# gsm.net
KiCad netlist of a schematic drawn in EAGLE
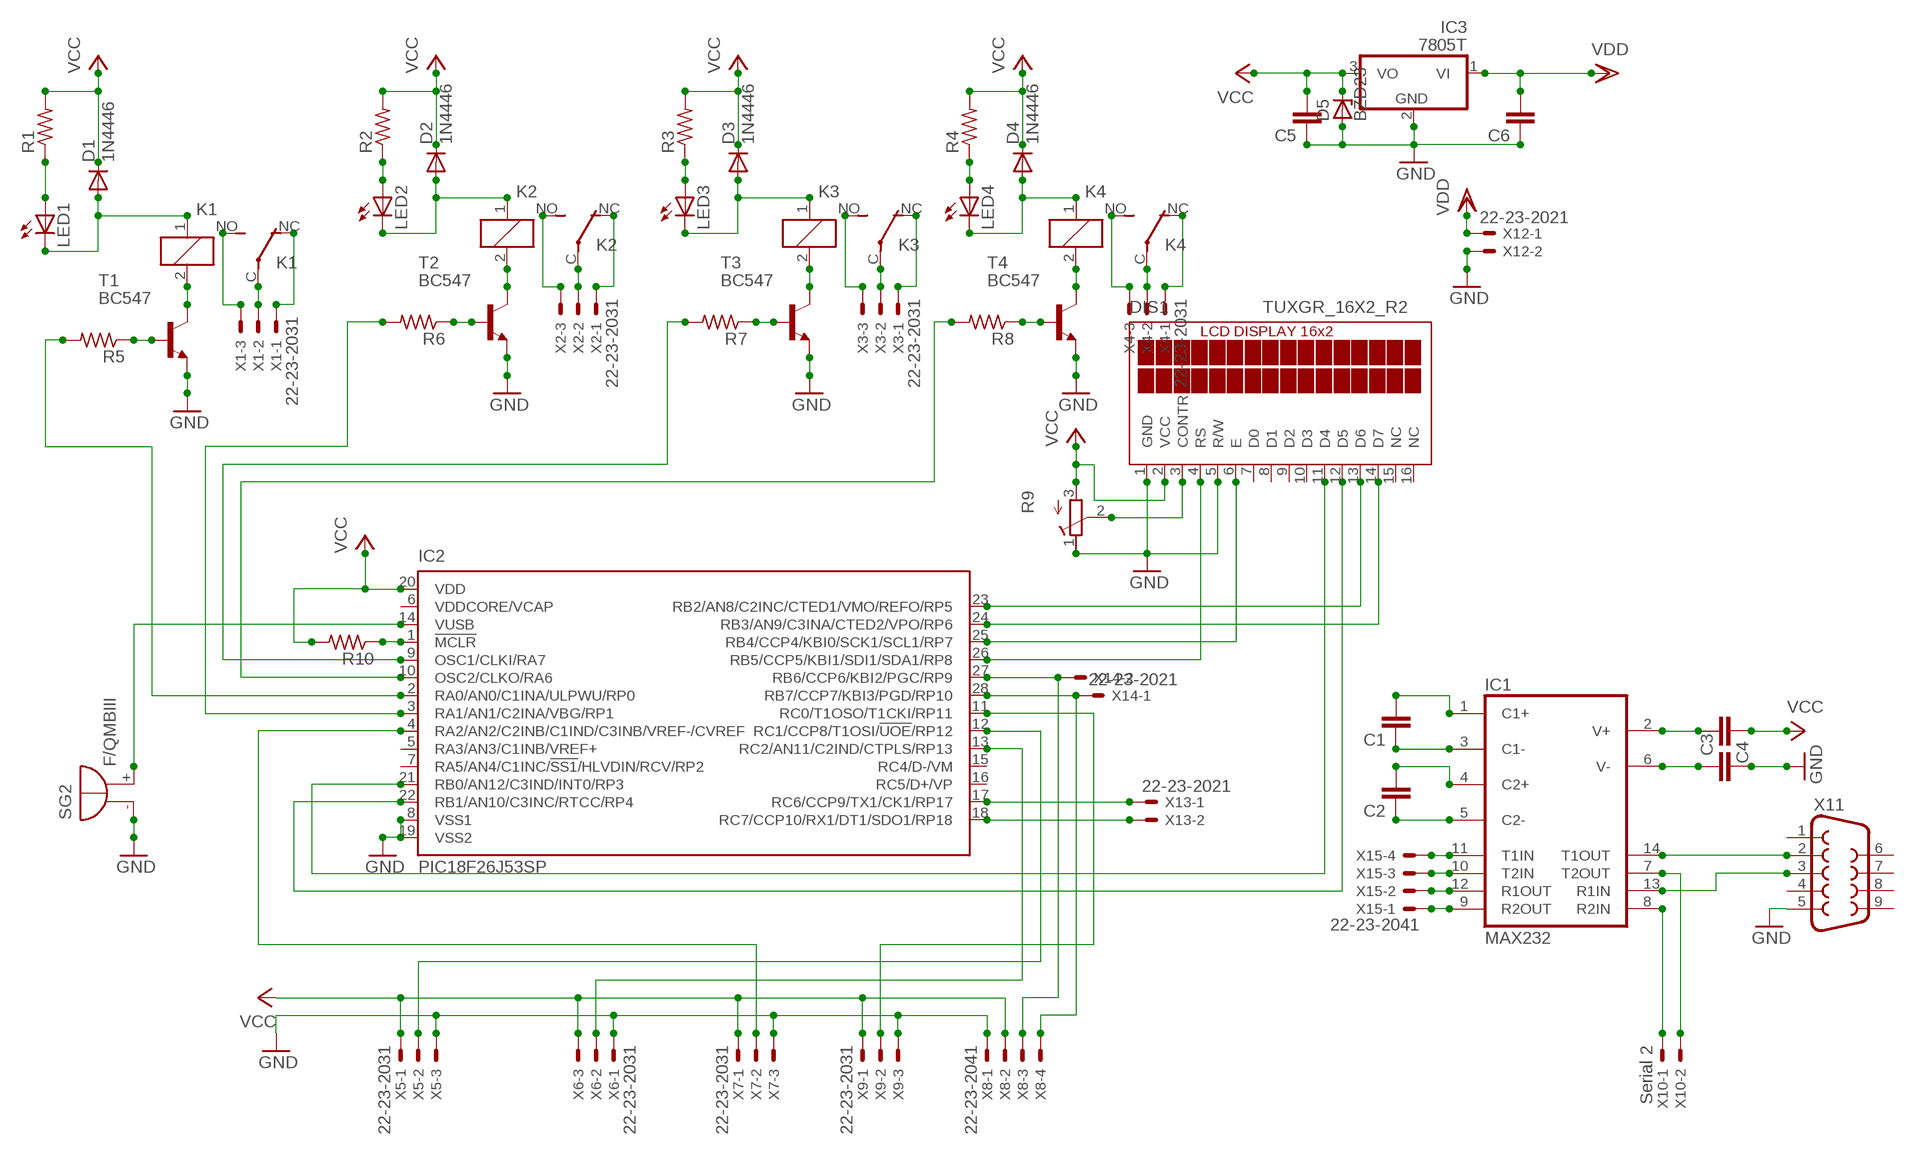
[diagram p0: schematic, sheet 1]

(export (version "E")
  (design (tool "Eeschema 10.0.6"))
  (components
    (comp (ref "C1")
      (value "C2.5/2")
      (footprint "eagle-import:C2.5-2")
      (libsource (lib "eagle-import") (part "C2.5/2"))
    )
    (comp (ref "C2")
      (value "C2.5/2")
      (footprint "eagle-import:C2.5-2")
      (libsource (lib "eagle-import") (part "C2.5/2"))
    )
    (comp (ref "C3")
      (value "C2.5/2")
      (footprint "eagle-import:C2.5-2")
      (libsource (lib "eagle-import") (part "C2.5/2"))
    )
    (comp (ref "C4")
      (value "C2.5/2")
      (footprint "eagle-import:C2.5-2")
      (libsource (lib "eagle-import") (part "C2.5/2"))
    )
    (comp (ref "C5")
      (value "C2.5/2")
      (footprint "eagle-import:C2.5-2")
      (libsource (lib "eagle-import") (part "C2.5/2"))
    )
    (comp (ref "C6")
      (value "C2.5/2")
      (footprint "eagle-import:C2.5-2")
      (libsource (lib "eagle-import") (part "C2.5/2"))
    )
    (comp (ref "D1")
      (value "1N4446")
      (footprint "eagle-import:DO35-10")
      (libsource (lib "eagle-import") (part "1N4446"))
    )
    (comp (ref "D2")
      (value "1N4446")
      (footprint "eagle-import:DO35-10")
      (libsource (lib "eagle-import") (part "1N4446"))
    )
    (comp (ref "D3")
      (value "1N4446")
      (footprint "eagle-import:DO35-10")
      (libsource (lib "eagle-import") (part "1N4446"))
    )
    (comp (ref "D4")
      (value "1N4446")
      (footprint "eagle-import:DO35-10")
      (libsource (lib "eagle-import") (part "1N4446"))
    )
    (comp (ref "D5")
      (value "BZD23")
      (footprint "eagle-import:SOD81")
      (libsource (lib "eagle-import") (part "BZD23"))
    )
    (comp (ref "DIS1")
      (value "TUXGR_16X2_R2")
      (footprint "eagle-import:TUXGR_16X2_R2")
      (libsource (lib "eagle-import") (part "TUXGR_16X2_R2"))
    )
    (comp (ref "IC1")
      (value "MAX232")
      (footprint "eagle-import:DIL16")
      (fields (field (name "MF") "MAXIM") (field (name "MPN") "MAX232ACPE+"))
      (libsource (lib "eagle-import") (part "MAX232"))
    )
    (comp (ref "IC2")
      (value "PIC18F26J53SP")
      (footprint "eagle-import:DIL28-3")
      (fields (field (name "MPN") "PIC18F26J53-I/SP"))
      (libsource (lib "eagle-import") (part "PIC18F2J53SP6"))
    )
    (comp (ref "IC3")
      (value "7805T")
      (footprint "eagle-import:TO220H")
      (libsource (lib "eagle-import") (part "78T05"))
    )
    (comp (ref "K1")
      (value "JJM1-12V")
      (footprint "eagle-import:JJM1C")
      (fields (field (name "MF") "AROMAT/ MATSUSHITA"))
      (libsource (lib "eagle-import") (part "JJM1-12V"))
    )
    (comp (ref "K2")
      (value "JJM1-12V")
      (footprint "eagle-import:JJM1C")
      (fields (field (name "MF") "AROMAT/ MATSUSHITA"))
      (libsource (lib "eagle-import") (part "JJM1-12V"))
    )
    (comp (ref "K3")
      (value "JJM1-12V")
      (footprint "eagle-import:JJM1C")
      (fields (field (name "MF") "AROMAT/ MATSUSHITA"))
      (libsource (lib "eagle-import") (part "JJM1-12V"))
    )
    (comp (ref "K4")
      (value "JJM1-12V")
      (footprint "eagle-import:JJM1C")
      (fields (field (name "MF") "AROMAT/ MATSUSHITA"))
      (libsource (lib "eagle-import") (part "JJM1-12V"))
    )
    (comp (ref "LED1")
      (value "LED3MM")
      (footprint "eagle-import:LED3MM")
      (libsource (lib "eagle-import") (part "LED3MM"))
    )
    (comp (ref "LED2")
      (value "LED3MM")
      (footprint "eagle-import:LED3MM")
      (libsource (lib "eagle-import") (part "LED3MM"))
    )
    (comp (ref "LED3")
      (value "LED3MM")
      (footprint "eagle-import:LED3MM")
      (libsource (lib "eagle-import") (part "LED3MM"))
    )
    (comp (ref "LED4")
      (value "LED3MM")
      (footprint "eagle-import:LED3MM")
      (libsource (lib "eagle-import") (part "LED3MM"))
    )
    (comp (ref "R1")
      (value "R-US_0207/10")
      (footprint "eagle-import:0207_10")
      (libsource (lib "eagle-import") (part "R-US_0207/10"))
    )
    (comp (ref "R2")
      (value "R-US_0207/10")
      (footprint "eagle-import:0207_10")
      (libsource (lib "eagle-import") (part "R-US_0207/10"))
    )
    (comp (ref "R3")
      (value "R-US_0207/10")
      (footprint "eagle-import:0207_10")
      (libsource (lib "eagle-import") (part "R-US_0207/10"))
    )
    (comp (ref "R4")
      (value "R-US_0207/10")
      (footprint "eagle-import:0207_10")
      (libsource (lib "eagle-import") (part "R-US_0207/10"))
    )
    (comp (ref "R5")
      (value "R-US_0207/10")
      (footprint "eagle-import:0207_10")
      (libsource (lib "eagle-import") (part "R-US_0207/10"))
    )
    (comp (ref "R6")
      (value "R-US_0207/10")
      (footprint "eagle-import:0207_10")
      (libsource (lib "eagle-import") (part "R-US_0207/10"))
    )
    (comp (ref "R7")
      (value "R-US_0207/10")
      (footprint "eagle-import:0207_10")
      (libsource (lib "eagle-import") (part "R-US_0207/10"))
    )
    (comp (ref "R8")
      (value "R-US_0207/10")
      (footprint "eagle-import:0207_10")
      (libsource (lib "eagle-import") (part "R-US_0207/10"))
    )
    (comp (ref "R9")
      (value "R-TRIMMT93YA")
      (footprint "eagle-import:RTRIMT93YA")
      (libsource (lib "eagle-import") (part "R-TRIMMT93YA"))
    )
    (comp (ref "R10")
      (value "R-US_0207/10")
      (footprint "eagle-import:0207_10")
      (libsource (lib "eagle-import") (part "R-US_0207/10"))
    )
    (comp (ref "SG2")
      (value "F/QMBIII")
      (footprint "eagle-import:F_QMBIII")
      (libsource (lib "eagle-import") (part "F/QMBIII"))
    )
    (comp (ref "T1")
      (value "BC547")
      (footprint "eagle-import:TO92")
      (libsource (lib "eagle-import") (part "BC547"))
    )
    (comp (ref "T2")
      (value "BC547")
      (footprint "eagle-import:TO92")
      (libsource (lib "eagle-import") (part "BC547"))
    )
    (comp (ref "T3")
      (value "BC547")
      (footprint "eagle-import:TO92")
      (libsource (lib "eagle-import") (part "BC547"))
    )
    (comp (ref "T4")
      (value "BC547")
      (footprint "eagle-import:TO92")
      (libsource (lib "eagle-import") (part "BC547"))
    )
    (comp (ref "X1")
      (value "22-23-2031")
      (footprint "eagle-import:22-23-2031")
      (fields (field (name "MF") "MOLEX"))
      (libsource (lib "eagle-import") (part "22-23-2031"))
    )
    (comp (ref "X2")
      (value "22-23-2031")
      (footprint "eagle-import:22-23-2031")
      (fields (field (name "MF") "MOLEX"))
      (libsource (lib "eagle-import") (part "22-23-2031"))
    )
    (comp (ref "X3")
      (value "22-23-2031")
      (footprint "eagle-import:22-23-2031")
      (fields (field (name "MF") "MOLEX"))
      (libsource (lib "eagle-import") (part "22-23-2031"))
    )
    (comp (ref "X4")
      (value "22-23-2031")
      (footprint "eagle-import:22-23-2031")
      (fields (field (name "MF") "MOLEX"))
      (libsource (lib "eagle-import") (part "22-23-2031"))
    )
    (comp (ref "X5")
      (value "22-23-2031")
      (footprint "eagle-import:22-23-2031")
      (fields (field (name "MF") "MOLEX"))
      (libsource (lib "eagle-import") (part "22-23-2031"))
    )
    (comp (ref "X6")
      (value "22-23-2031")
      (footprint "eagle-import:22-23-2031")
      (fields (field (name "MF") "MOLEX"))
      (libsource (lib "eagle-import") (part "22-23-2031"))
    )
    (comp (ref "X7")
      (value "22-23-2031")
      (footprint "eagle-import:22-23-2031")
      (fields (field (name "MF") "MOLEX"))
      (libsource (lib "eagle-import") (part "22-23-2031"))
    )
    (comp (ref "X8")
      (value "22-23-2041")
      (footprint "eagle-import:22-23-2041")
      (fields (field (name "MF") "MOLEX"))
      (libsource (lib "eagle-import") (part "22-23-2041"))
    )
    (comp (ref "X9")
      (value "22-23-2031")
      (footprint "eagle-import:22-23-2031")
      (fields (field (name "MF") "MOLEX"))
      (libsource (lib "eagle-import") (part "22-23-2031"))
    )
    (comp (ref "X10")
      (value "Serial 2")
      (footprint "eagle-import:22-23-2021")
      (fields (field (name "MF") "MOLEX") (field (name "MPN") "22-23-2021"))
      (libsource (lib "eagle-import") (part "22-23-2021"))
    )
    (comp (ref "X11")
      (value "F09H")
      (footprint "eagle-import:F09H")
      (libsource (lib "eagle-import") (part "F09H"))
    )
    (comp (ref "X12")
      (value "22-23-2021")
      (footprint "eagle-import:22-23-2021")
      (fields (field (name "MF") "MOLEX"))
      (libsource (lib "eagle-import") (part "22-23-2021"))
    )
    (comp (ref "X13")
      (value "22-23-2021")
      (footprint "eagle-import:22-23-2021")
      (fields (field (name "MF") "MOLEX"))
      (libsource (lib "eagle-import") (part "22-23-2021"))
    )
    (comp (ref "X14")
      (value "22-23-2021")
      (footprint "eagle-import:22-23-2021")
      (fields (field (name "MF") "MOLEX"))
      (libsource (lib "eagle-import") (part "22-23-2021"))
    )
    (comp (ref "X15")
      (value "22-23-2041")
      (footprint "eagle-import:22-23-2041")
      (fields (field (name "MF") "MOLEX"))
      (libsource (lib "eagle-import") (part "22-23-2041"))
    )
  )
  (nets
    (net (code "1") (name "GND") (class "Default")
      (node (ref "C3") (pin "2") (pinfunction "2_2") (pintype "passive"))
      (node (ref "C5") (pin "1") (pinfunction "1_1") (pintype "passive"))
      (node (ref "C6") (pin "1") (pinfunction "1_1") (pintype "passive"))
      (node (ref "D5") (pin "A") (pinfunction "A_A") (pintype "passive"))
      (node (ref "DIS1") (pin "1") (pinfunction "GND_1") (pintype "power_in"))
      (node (ref "DIS1") (pin "5") (pinfunction "R/W_5") (pintype "input"))
      (node (ref "IC2") (pin "19") (pinfunction "VSS2_19") (pintype "input"))
      (node (ref "IC2") (pin "8") (pinfunction "VSS1_8") (pintype "input"))
      (node (ref "IC3") (pin "2") (pinfunction "GND_2") (pintype "passive"))
      (node (ref "R9") (pin "1") (pinfunction "E_1") (pintype "passive"))
      (node (ref "SG2") (pin "-") (pinfunction "+_-") (pintype "passive"))
      (node (ref "T1") (pin "1") (pinfunction "E_1") (pintype "passive"))
      (node (ref "T2") (pin "1") (pinfunction "E_1") (pintype "passive"))
      (node (ref "T3") (pin "1") (pinfunction "E_1") (pintype "passive"))
      (node (ref "T4") (pin "1") (pinfunction "E_1") (pintype "passive"))
      (node (ref "X11") (pin "5") (pinfunction "5_5") (pintype "passive"))
      (node (ref "X12") (pin "2") (pinfunction "S_2") (pintype "passive"))
      (node (ref "X5") (pin "3") (pinfunction "S_3") (pintype "passive"))
      (node (ref "X6") (pin "1") (pinfunction "S_1") (pintype "passive"))
      (node (ref "X7") (pin "3") (pinfunction "S_3") (pintype "passive"))
      (node (ref "X8") (pin "1") (pinfunction "S_1") (pintype "passive"))
      (node (ref "X9") (pin "3") (pinfunction "S_3") (pintype "passive"))
    )
    (net (code "2") (name "Net-(DIS1-CONTR)") (class "Default")
      (node (ref "DIS1") (pin "3") (pinfunction "CONTR_3") (pintype "input"))
      (node (ref "R9") (pin "2") (pinfunction "S_2") (pintype "passive"))
    )
    (net (code "3") (name "Net-(DIS1-D4)") (class "Default")
      (node (ref "DIS1") (pin "11") (pinfunction "D4_11") (pintype "input"))
      (node (ref "IC2") (pin "21") (pinfunction "RB0/AN12/C3IND/INT0/RP3_21") (pintype "bidirectional"))
    )
    (net (code "4") (name "Net-(DIS1-D5)") (class "Default")
      (node (ref "DIS1") (pin "12") (pinfunction "D5_12") (pintype "input"))
      (node (ref "IC2") (pin "22") (pinfunction "RB1/AN10/C3INC/RTCC/RP4_22") (pintype "bidirectional"))
    )
    (net (code "5") (name "Net-(DIS1-D6)") (class "Default")
      (node (ref "DIS1") (pin "13") (pinfunction "D6_13") (pintype "input"))
      (node (ref "IC2") (pin "23") (pinfunction "RB2/AN8/C2INC/CTED1/VMO/REFO/RP5_23") (pintype "bidirectional"))
    )
    (net (code "6") (name "Net-(DIS1-D7)") (class "Default")
      (node (ref "DIS1") (pin "14") (pinfunction "D7_14") (pintype "input"))
      (node (ref "IC2") (pin "24") (pinfunction "RB3/AN9/C3INA/CTED2/VPO/RP6_24") (pintype "bidirectional"))
    )
    (net (code "7") (name "Net-(DIS1-E)") (class "Default")
      (node (ref "DIS1") (pin "6") (pinfunction "E_6") (pintype "input"))
      (node (ref "IC2") (pin "25") (pinfunction "RB4/CCP4/KBI0/SCK1/SCL1/RP7_25") (pintype "bidirectional"))
    )
    (net (code "8") (name "Net-(DIS1-RS)") (class "Default")
      (node (ref "DIS1") (pin "4") (pinfunction "RS_4") (pintype "input"))
      (node (ref "IC2") (pin "26") (pinfunction "RB5/CCP5/KBI1/SDI1/SDA1/RP8_26") (pintype "bidirectional"))
    )
    (net (code "9") (name "Net-(IC1A-C1+)") (class "Default")
      (node (ref "C1") (pin "2") (pinfunction "2_2") (pintype "passive"))
      (node (ref "IC1") (pin "1") (pinfunction "C1+_1") (pintype "bidirectional"))
    )
    (net (code "10") (name "Net-(IC1A-C1-)") (class "Default")
      (node (ref "C1") (pin "1") (pinfunction "1_1") (pintype "passive"))
      (node (ref "IC1") (pin "3") (pinfunction "C1-_3") (pintype "bidirectional"))
    )
    (net (code "11") (name "Net-(IC1A-C2+)") (class "Default")
      (node (ref "C2") (pin "2") (pinfunction "2_2") (pintype "passive"))
      (node (ref "IC1") (pin "4") (pinfunction "C2+_4") (pintype "bidirectional"))
    )
    (net (code "12") (name "Net-(IC1A-C2-)") (class "Default")
      (node (ref "C2") (pin "1") (pinfunction "1_1") (pintype "passive"))
      (node (ref "IC1") (pin "5") (pinfunction "C2-_5") (pintype "bidirectional"))
    )
    (net (code "13") (name "Net-(IC1A-R1IN)") (class "Default")
      (node (ref "IC1") (pin "13") (pinfunction "R1IN_13") (pintype "input"))
      (node (ref "X11") (pin "3") (pinfunction "3_3") (pintype "passive"))
    )
    (net (code "14") (name "Net-(IC1A-R1OUT)") (class "Default")
      (node (ref "IC1") (pin "12") (pinfunction "R1OUT_12") (pintype "output"))
      (node (ref "X15") (pin "2") (pinfunction "S_2") (pintype "passive"))
    )
    (net (code "15") (name "Net-(IC1A-R2IN)") (class "Default")
      (node (ref "IC1") (pin "8") (pinfunction "R2IN_8") (pintype "input"))
      (node (ref "X10") (pin "1") (pinfunction "S_1") (pintype "passive"))
    )
    (net (code "16") (name "Net-(IC1A-R2OUT)") (class "Default")
      (node (ref "IC1") (pin "9") (pinfunction "R2OUT_9") (pintype "output"))
      (node (ref "X15") (pin "1") (pinfunction "S_1") (pintype "passive"))
    )
    (net (code "17") (name "Net-(IC1A-T1IN)") (class "Default")
      (node (ref "IC1") (pin "11") (pinfunction "T1IN_11") (pintype "input"))
      (node (ref "X15") (pin "4") (pinfunction "S_4") (pintype "passive"))
    )
    (net (code "18") (name "Net-(IC1A-T1OUT)") (class "Default")
      (node (ref "IC1") (pin "14") (pinfunction "T1OUT_14") (pintype "output"))
      (node (ref "X11") (pin "2") (pinfunction "2_2") (pintype "passive"))
    )
    (net (code "19") (name "Net-(IC1A-T2IN)") (class "Default")
      (node (ref "IC1") (pin "10") (pinfunction "T2IN_10") (pintype "input"))
      (node (ref "X15") (pin "3") (pinfunction "S_3") (pintype "passive"))
    )
    (net (code "20") (name "Net-(IC1A-T2OUT)") (class "Default")
      (node (ref "IC1") (pin "7") (pinfunction "T2OUT_7") (pintype "output"))
      (node (ref "X10") (pin "2") (pinfunction "S_2") (pintype "passive"))
    )
    (net (code "21") (name "Net-(IC1A-V+)") (class "Default")
      (node (ref "C4") (pin "2") (pinfunction "2_2") (pintype "passive"))
      (node (ref "IC1") (pin "2") (pinfunction "V+_2") (pintype "bidirectional"))
    )
    (net (code "22") (name "Net-(IC1A-V-)") (class "Default")
      (node (ref "C3") (pin "1") (pinfunction "1_1") (pintype "passive"))
      (node (ref "IC1") (pin "6") (pinfunction "V-_6") (pintype "bidirectional"))
    )
    (net (code "23") (name "Net-(IC2-OSC1{slash}CLKI{slash}RA7)") (class "Default")
      (node (ref "IC2") (pin "9") (pinfunction "OSC1/CLKI/RA7_9") (pintype "bidirectional"))
      (node (ref "R7") (pin "2") (pinfunction "2_2") (pintype "passive"))
    )
    (net (code "24") (name "Net-(IC2-OSC2{slash}CLKO{slash}RA6)") (class "Default")
      (node (ref "IC2") (pin "10") (pinfunction "OSC2/CLKO/RA6_10") (pintype "bidirectional"))
      (node (ref "R8") (pin "2") (pinfunction "2_2") (pintype "passive"))
    )
    (net (code "25") (name "Net-(IC2-RA0{slash}AN0{slash}C1INA{slash}ULPWU{slash}RP0)") (class "Default")
      (node (ref "IC2") (pin "2") (pinfunction "RA0/AN0/C1INA/ULPWU/RP0_2") (pintype "bidirectional"))
      (node (ref "R5") (pin "2") (pinfunction "2_2") (pintype "passive"))
    )
    (net (code "26") (name "Net-(IC2-RA1{slash}AN1{slash}C2INA{slash}VBG{slash}RP1)") (class "Default")
      (node (ref "IC2") (pin "3") (pinfunction "RA1/AN1/C2INA/VBG/RP1_3") (pintype "bidirectional"))
      (node (ref "R6") (pin "2") (pinfunction "2_2") (pintype "passive"))
    )
    (net (code "27") (name "Net-(IC2-RA2{slash}AN2{slash}C2INB{slash}C1IND{slash}C3INB{slash}VREF-{slash}CVREF)") (class "Default")
      (node (ref "IC2") (pin "4") (pinfunction "RA2/AN2/C2INB/C1IND/C3INB/VREF-/CVREF_4") (pintype "bidirectional"))
      (node (ref "X7") (pin "2") (pinfunction "S_2") (pintype "passive"))
    )
    (net (code "28") (name "Net-(IC2-RB6{slash}CCP6{slash}KBI2{slash}PGC{slash}RP9)") (class "Default")
      (node (ref "IC2") (pin "27") (pinfunction "RB6/CCP6/KBI2/PGC/RP9_27") (pintype "bidirectional"))
      (node (ref "X14") (pin "2") (pinfunction "S_2") (pintype "passive"))
      (node (ref "X8") (pin "3") (pinfunction "S_3") (pintype "passive"))
    )
    (net (code "29") (name "Net-(IC2-RB7{slash}CCP7{slash}KBI3{slash}PGD{slash}RP10)") (class "Default")
      (node (ref "IC2") (pin "28") (pinfunction "RB7/CCP7/KBI3/PGD/RP10_28") (pintype "bidirectional"))
      (node (ref "X14") (pin "1") (pinfunction "S_1") (pintype "passive"))
      (node (ref "X8") (pin "4") (pinfunction "S_4") (pintype "passive"))
    )
    (net (code "30") (name "Net-(IC2-RC0{slash}T1OSO{slash}T1CKI{slash}RP11)") (class "Default")
      (node (ref "IC2") (pin "11") (pinfunction "RC0/T1OSO/T1CKI/RP11_11") (pintype "bidirectional"))
      (node (ref "X9") (pin "2") (pinfunction "S_2") (pintype "passive"))
    )
    (net (code "31") (name "Net-(IC2-RC1{slash}CCP8{slash}T1OSI{slash}~{UOE}{slash}RP12)") (class "Default")
      (node (ref "IC2") (pin "12") (pinfunction "RC1/CCP8/T1OSI/~{UOE}/RP12_12") (pintype "bidirectional"))
      (node (ref "X5") (pin "2") (pinfunction "S_2") (pintype "passive"))
    )
    (net (code "32") (name "Net-(IC2-RC2{slash}AN11{slash}C2IND{slash}CTPLS{slash}RP13)") (class "Default")
      (node (ref "IC2") (pin "13") (pinfunction "RC2/AN11/C2IND/CTPLS/RP13_13") (pintype "bidirectional"))
      (node (ref "X6") (pin "2") (pinfunction "S_2") (pintype "passive"))
    )
    (net (code "33") (name "Net-(IC2-RC6{slash}CCP9{slash}TX1{slash}CK1{slash}RP17)") (class "Default")
      (node (ref "IC2") (pin "17") (pinfunction "RC6/CCP9/TX1/CK1/RP17_17") (pintype "bidirectional"))
      (node (ref "X13") (pin "1") (pinfunction "S_1") (pintype "passive"))
    )
    (net (code "34") (name "Net-(IC2-RC7{slash}CCP10{slash}RX1{slash}DT1{slash}SDO1{slash}RP18)") (class "Default")
      (node (ref "IC2") (pin "18") (pinfunction "RC7/CCP10/RX1/DT1/SDO1/RP18_18") (pintype "bidirectional"))
      (node (ref "X13") (pin "2") (pinfunction "S_2") (pintype "passive"))
    )
    (net (code "35") (name "Net-(IC2-VUSB)") (class "Default")
      (node (ref "IC2") (pin "14") (pinfunction "VUSB_14") (pintype "input"))
      (node (ref "SG2") (pin "+") (pinfunction "-_+") (pintype "passive"))
    )
    (net (code "36") (name "Net-(IC2-~{MCLR})") (class "Default")
      (node (ref "IC2") (pin "1") (pinfunction "~{MCLR}_1") (pintype "input"))
      (node (ref "R10") (pin "1") (pinfunction "1_1") (pintype "passive"))
    )
    (net (code "37") (name "Net-(K1B-O)") (class "Default")
      (node (ref "K1") (pin "NC") (pinfunction "O_NC") (pintype "passive"))
      (node (ref "X1") (pin "1") (pinfunction "S_1") (pintype "passive"))
    )
    (net (code "38") (name "Net-(K1B-P)") (class "Default")
      (node (ref "K1") (pin "C") (pinfunction "P_C") (pintype "passive"))
      (node (ref "X1") (pin "2") (pinfunction "S_2") (pintype "passive"))
    )
    (net (code "39") (name "Net-(K1B-S)") (class "Default")
      (node (ref "K1") (pin "NO") (pinfunction "S_NO") (pintype "passive"))
      (node (ref "X1") (pin "3") (pinfunction "S_3") (pintype "passive"))
    )
    (net (code "40") (name "Net-(K2B-O)") (class "Default")
      (node (ref "K2") (pin "NC") (pinfunction "O_NC") (pintype "passive"))
      (node (ref "X2") (pin "1") (pinfunction "S_1") (pintype "passive"))
    )
    (net (code "41") (name "Net-(K2B-P)") (class "Default")
      (node (ref "K2") (pin "C") (pinfunction "P_C") (pintype "passive"))
      (node (ref "X2") (pin "2") (pinfunction "S_2") (pintype "passive"))
    )
    (net (code "42") (name "Net-(K2B-S)") (class "Default")
      (node (ref "K2") (pin "NO") (pinfunction "S_NO") (pintype "passive"))
      (node (ref "X2") (pin "3") (pinfunction "S_3") (pintype "passive"))
    )
    (net (code "43") (name "Net-(K3B-O)") (class "Default")
      (node (ref "K3") (pin "NC") (pinfunction "O_NC") (pintype "passive"))
      (node (ref "X3") (pin "1") (pinfunction "S_1") (pintype "passive"))
    )
    (net (code "44") (name "Net-(K3B-P)") (class "Default")
      (node (ref "K3") (pin "C") (pinfunction "P_C") (pintype "passive"))
      (node (ref "X3") (pin "2") (pinfunction "S_2") (pintype "passive"))
    )
    (net (code "45") (name "Net-(K3B-S)") (class "Default")
      (node (ref "K3") (pin "NO") (pinfunction "S_NO") (pintype "passive"))
      (node (ref "X3") (pin "3") (pinfunction "S_3") (pintype "passive"))
    )
    (net (code "46") (name "Net-(K4B-O)") (class "Default")
      (node (ref "K4") (pin "NC") (pinfunction "O_NC") (pintype "passive"))
      (node (ref "X4") (pin "1") (pinfunction "S_1") (pintype "passive"))
    )
    (net (code "47") (name "Net-(K4B-P)") (class "Default")
      (node (ref "K4") (pin "C") (pinfunction "P_C") (pintype "passive"))
      (node (ref "X4") (pin "2") (pinfunction "S_2") (pintype "passive"))
    )
    (net (code "48") (name "Net-(K4B-S)") (class "Default")
      (node (ref "K4") (pin "NO") (pinfunction "S_NO") (pintype "passive"))
      (node (ref "X4") (pin "3") (pinfunction "S_3") (pintype "passive"))
    )
    (net (code "49") (name "Net-(LED1-C)") (class "Default")
      (node (ref "D1") (pin "A") (pinfunction "A_A") (pintype "passive"))
      (node (ref "K1") (pin "1") (pinfunction "1_1") (pintype "passive"))
      (node (ref "LED1") (pin "K") (pinfunction "C_K") (pintype "passive"))
    )
    (net (code "50") (name "Net-(LED1-PadA)") (class "Default")
      (node (ref "LED1") (pin "A") (pinfunction "A_A") (pintype "passive"))
      (node (ref "R1") (pin "1") (pinfunction "1_1") (pintype "passive"))
    )
    (net (code "51") (name "Net-(LED2-C)") (class "Default")
      (node (ref "D2") (pin "A") (pinfunction "A_A") (pintype "passive"))
      (node (ref "K2") (pin "1") (pinfunction "1_1") (pintype "passive"))
      (node (ref "LED2") (pin "K") (pinfunction "C_K") (pintype "passive"))
    )
    (net (code "52") (name "Net-(LED2-PadA)") (class "Default")
      (node (ref "LED2") (pin "A") (pinfunction "A_A") (pintype "passive"))
      (node (ref "R2") (pin "1") (pinfunction "1_1") (pintype "passive"))
    )
    (net (code "53") (name "Net-(LED3-C)") (class "Default")
      (node (ref "D3") (pin "A") (pinfunction "A_A") (pintype "passive"))
      (node (ref "K3") (pin "1") (pinfunction "1_1") (pintype "passive"))
      (node (ref "LED3") (pin "K") (pinfunction "C_K") (pintype "passive"))
    )
    (net (code "54") (name "Net-(LED3-PadA)") (class "Default")
      (node (ref "LED3") (pin "A") (pinfunction "A_A") (pintype "passive"))
      (node (ref "R3") (pin "1") (pinfunction "1_1") (pintype "passive"))
    )
    (net (code "55") (name "Net-(LED4-C)") (class "Default")
      (node (ref "D4") (pin "A") (pinfunction "A_A") (pintype "passive"))
      (node (ref "K4") (pin "1") (pinfunction "1_1") (pintype "passive"))
      (node (ref "LED4") (pin "K") (pinfunction "C_K") (pintype "passive"))
    )
    (net (code "56") (name "Net-(LED4-PadA)") (class "Default")
      (node (ref "LED4") (pin "A") (pinfunction "A_A") (pintype "passive"))
      (node (ref "R4") (pin "1") (pinfunction "1_1") (pintype "passive"))
    )
    (net (code "57") (name "Net-(T1-B)") (class "Default")
      (node (ref "R5") (pin "1") (pinfunction "1_1") (pintype "passive"))
      (node (ref "T1") (pin "2") (pinfunction "B_2") (pintype "passive"))
    )
    (net (code "58") (name "Net-(T1-C)") (class "Default")
      (node (ref "K1") (pin "2") (pinfunction "2_2") (pintype "passive"))
      (node (ref "T1") (pin "3") (pinfunction "C_3") (pintype "passive"))
    )
    (net (code "59") (name "Net-(T2-B)") (class "Default")
      (node (ref "R6") (pin "1") (pinfunction "1_1") (pintype "passive"))
      (node (ref "T2") (pin "2") (pinfunction "B_2") (pintype "passive"))
    )
    (net (code "60") (name "Net-(T2-C)") (class "Default")
      (node (ref "K2") (pin "2") (pinfunction "2_2") (pintype "passive"))
      (node (ref "T2") (pin "3") (pinfunction "C_3") (pintype "passive"))
    )
    (net (code "61") (name "Net-(T3-B)") (class "Default")
      (node (ref "R7") (pin "1") (pinfunction "1_1") (pintype "passive"))
      (node (ref "T3") (pin "2") (pinfunction "B_2") (pintype "passive"))
    )
    (net (code "62") (name "Net-(T3-C)") (class "Default")
      (node (ref "K3") (pin "2") (pinfunction "2_2") (pintype "passive"))
      (node (ref "T3") (pin "3") (pinfunction "C_3") (pintype "passive"))
    )
    (net (code "63") (name "Net-(T4-B)") (class "Default")
      (node (ref "R8") (pin "1") (pinfunction "1_1") (pintype "passive"))
      (node (ref "T4") (pin "2") (pinfunction "B_2") (pintype "passive"))
    )
    (net (code "64") (name "Net-(T4-C)") (class "Default")
      (node (ref "K4") (pin "2") (pinfunction "2_2") (pintype "passive"))
      (node (ref "T4") (pin "3") (pinfunction "C_3") (pintype "passive"))
    )
    (net (code "65") (name "VCC") (class "Default")
      (node (ref "C4") (pin "1") (pinfunction "1_1") (pintype "passive"))
      (node (ref "C5") (pin "2") (pinfunction "2_2") (pintype "passive"))
      (node (ref "D1") (pin "C") (pinfunction "C_C") (pintype "passive"))
      (node (ref "D2") (pin "C") (pinfunction "C_C") (pintype "passive"))
      (node (ref "D3") (pin "C") (pinfunction "C_C") (pintype "passive"))
      (node (ref "D4") (pin "C") (pinfunction "C_C") (pintype "passive"))
      (node (ref "D5") (pin "C") (pinfunction "C_C") (pintype "passive"))
      (node (ref "DIS1") (pin "2") (pinfunction "VCC_2") (pintype "power_in"))
      (node (ref "IC2") (pin "20") (pinfunction "VDD_20") (pintype "input"))
      (node (ref "IC3") (pin "3") (pinfunction "VO_3") (pintype "passive"))
      (node (ref "R1") (pin "2") (pinfunction "2_2") (pintype "passive"))
      (node (ref "R10") (pin "2") (pinfunction "2_2") (pintype "passive"))
      (node (ref "R2") (pin "2") (pinfunction "2_2") (pintype "passive"))
      (node (ref "R3") (pin "2") (pinfunction "2_2") (pintype "passive"))
      (node (ref "R4") (pin "2") (pinfunction "2_2") (pintype "passive"))
      (node (ref "R9") (pin "3") (pinfunction "A_3") (pintype "passive"))
      (node (ref "X5") (pin "1") (pinfunction "S_1") (pintype "passive"))
      (node (ref "X6") (pin "3") (pinfunction "S_3") (pintype "passive"))
      (node (ref "X7") (pin "1") (pinfunction "S_1") (pintype "passive"))
      (node (ref "X8") (pin "2") (pinfunction "S_2") (pintype "passive"))
      (node (ref "X9") (pin "1") (pinfunction "S_1") (pintype "passive"))
    )
    (net (code "66") (name "VDD") (class "Default")
      (node (ref "C6") (pin "2") (pinfunction "2_2") (pintype "passive"))
      (node (ref "IC3") (pin "1") (pinfunction "VI_1") (pintype "input"))
      (node (ref "X12") (pin "1") (pinfunction "S_1") (pintype "passive"))
    )
    (net (code "67") (name "unconnected-(DIS1-D0-Pad7)") (class "Default")
      (node (ref "DIS1") (pin "7") (pinfunction "D0_7") (pintype "input"))
    )
    (net (code "68") (name "unconnected-(DIS1-D1-Pad8)") (class "Default")
      (node (ref "DIS1") (pin "8") (pinfunction "D1_8") (pintype "input"))
    )
    (net (code "69") (name "unconnected-(DIS1-D2-Pad9)") (class "Default")
      (node (ref "DIS1") (pin "9") (pinfunction "D2_9") (pintype "input"))
    )
    (net (code "70") (name "unconnected-(DIS1-D3-Pad10)") (class "Default")
      (node (ref "DIS1") (pin "10") (pinfunction "D3_10") (pintype "input"))
    )
    (net (code "71") (name "unconnected-(DIS1-NC-Pad15)") (class "Default")
      (node (ref "DIS1") (pin "15") (pinfunction "NC_15") (pintype "no_connect"))
    )
    (net (code "72") (name "unconnected-(DIS1-NC-Pad16)") (class "Default")
      (node (ref "DIS1") (pin "16") (pinfunction "NC_16") (pintype "no_connect"))
    )
    (net (code "73") (name "unconnected-(IC2-RA3{slash}AN3{slash}C1INB{slash}VREF+-Pad5)") (class "Default")
      (node (ref "IC2") (pin "5") (pinfunction "RA3/AN3/C1INB/VREF+_5") (pintype "bidirectional"))
    )
    (net (code "74") (name "unconnected-(IC2-RA5{slash}AN4{slash}C1INC{slash}~{SS1}{slash}HLVDIN{slash}RCV{slash}RP2-Pad7)") (class "Default")
      (node (ref "IC2") (pin "7") (pinfunction "RA5/AN4/C1INC/~{SS1}/HLVDIN/RCV/RP2_7") (pintype "bidirectional"))
    )
    (net (code "75") (name "unconnected-(IC2-RC4{slash}D-{slash}VM-Pad15)") (class "Default")
      (node (ref "IC2") (pin "15") (pinfunction "RC4/D-/VM_15") (pintype "bidirectional"))
    )
    (net (code "76") (name "unconnected-(IC2-RC5{slash}D+{slash}VP-Pad16)") (class "Default")
      (node (ref "IC2") (pin "16") (pinfunction "RC5/D+/VP_16") (pintype "bidirectional"))
    )
    (net (code "77") (name "unconnected-(IC2-VDDCORE{slash}VCAP-Pad6)") (class "Default")
      (node (ref "IC2") (pin "6") (pinfunction "VDDCORE/VCAP_6") (pintype "input"))
    )
    (net (code "78") (name "unconnected-(X11-Pad1)") (class "Default")
      (node (ref "X11") (pin "1") (pinfunction "1_1") (pintype "passive"))
    )
    (net (code "79") (name "unconnected-(X11-Pad4)") (class "Default")
      (node (ref "X11") (pin "4") (pinfunction "4_4") (pintype "passive"))
    )
    (net (code "80") (name "unconnected-(X11-Pad6)") (class "Default")
      (node (ref "X11") (pin "6") (pinfunction "6_6") (pintype "passive"))
    )
    (net (code "81") (name "unconnected-(X11-Pad7)") (class "Default")
      (node (ref "X11") (pin "7") (pinfunction "7_7") (pintype "passive"))
    )
    (net (code "82") (name "unconnected-(X11-Pad8)") (class "Default")
      (node (ref "X11") (pin "8") (pinfunction "8_8") (pintype "passive"))
    )
    (net (code "83") (name "unconnected-(X11-Pad9)") (class "Default")
      (node (ref "X11") (pin "9") (pinfunction "9_9") (pintype "passive"))
    )
  )
)
